# l3lanSpy.net
KiCad netlist of a schematic drawn in EAGLE
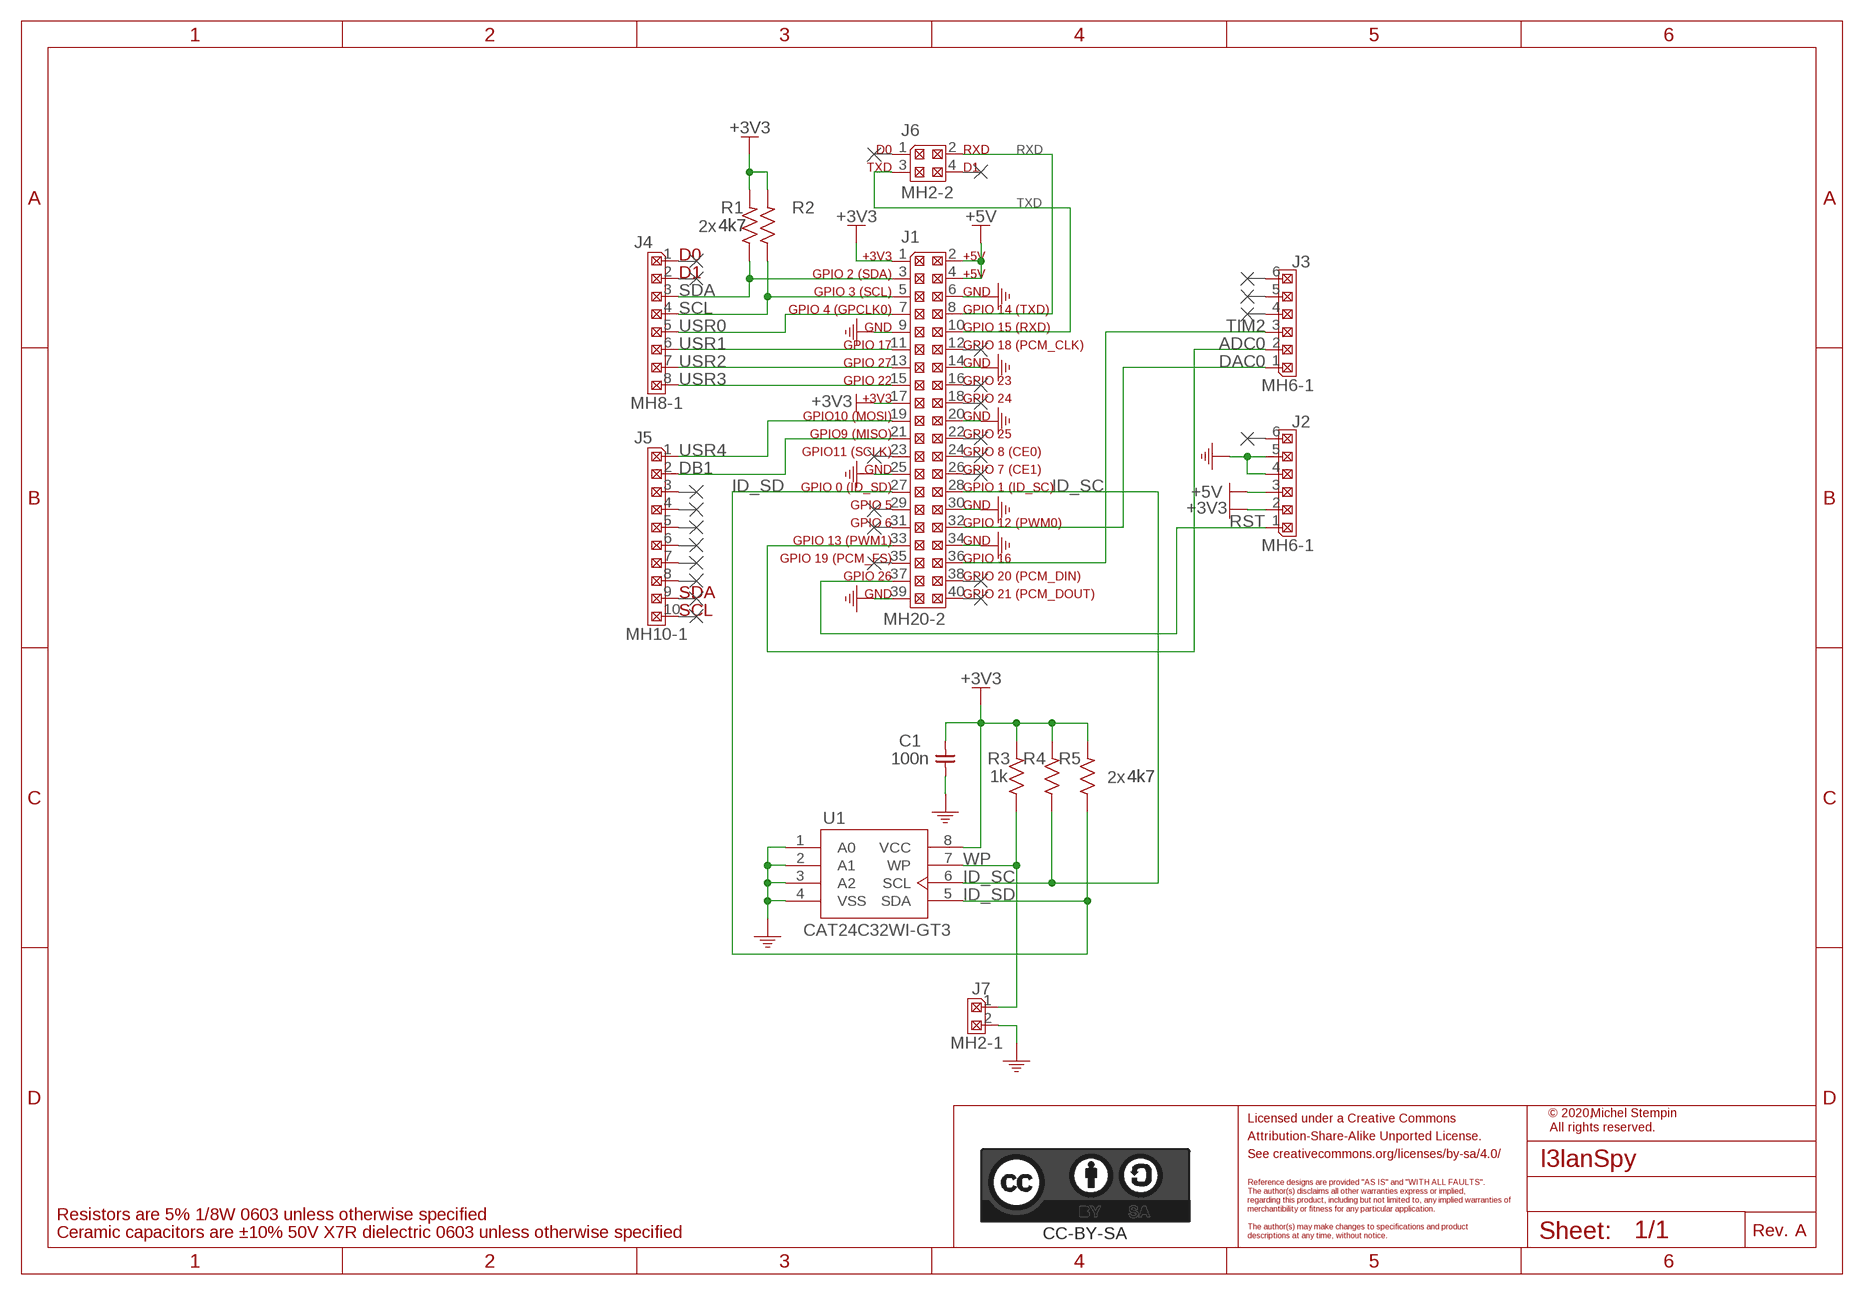
[diagram p0: schematic, sheet 1]

(export (version "E")
  (design (tool "Eeschema 10.0.6"))
  (components
    (comp (ref "C1")
      (value "100n")
      (footprint "eagle-import:C0603")
      (libsource (lib "eagle-import") (part "CAP_0603"))
    )
    (comp (ref "J1")
      (value "MH20-2")
      (footprint "eagle-import:MH20-2-0.1")
      (libsource (lib "eagle-import") (part "MH20-2"))
    )
    (comp (ref "J2")
      (value "MH6-1")
      (footprint "eagle-import:MH6-1-0.1")
      (libsource (lib "eagle-import") (part "MH6-1"))
    )
    (comp (ref "J3")
      (value "MH6-1")
      (footprint "eagle-import:MH6-1-0.1")
      (libsource (lib "eagle-import") (part "MH6-1"))
    )
    (comp (ref "J4")
      (value "MH8-1")
      (footprint "eagle-import:MH8-1-0.1")
      (libsource (lib "eagle-import") (part "MH8-1"))
    )
    (comp (ref "J5")
      (value "MH10-1")
      (footprint "eagle-import:MH10-1-0.1")
      (libsource (lib "eagle-import") (part "MH10-1"))
    )
    (comp (ref "J6")
      (value "MH2-2")
      (footprint "eagle-import:MH2-2-0.1")
      (libsource (lib "eagle-import") (part "MH2-2"))
    )
    (comp (ref "J7")
      (value "MH2-1")
      (footprint "eagle-import:MH2-1-0.1")
      (libsource (lib "eagle-import") (part "MH2-1"))
    )
    (comp (ref "LOGO1")
      (value "CC-BY-SA_LOGO")
      (footprint "eagle-import:CC-BY-SA_LOGO")
      (libsource (lib "eagle-import") (part "CC-BY-SA_LOGO"))
    )
    (comp (ref "R1")
      (value "4k7")
      (footprint "eagle-import:R0603")
      (libsource (lib "eagle-import") (part "RES_0603"))
    )
    (comp (ref "R2")
      (value "4k7")
      (footprint "eagle-import:R0603")
      (libsource (lib "eagle-import") (part "RES_0603"))
    )
    (comp (ref "R3")
      (value "1k")
      (footprint "eagle-import:R0603")
      (libsource (lib "eagle-import") (part "RES_0603"))
    )
    (comp (ref "R4")
      (value "4k7")
      (footprint "eagle-import:R0603")
      (libsource (lib "eagle-import") (part "RES_0603"))
    )
    (comp (ref "R5")
      (value "4k7")
      (footprint "eagle-import:R0603")
      (libsource (lib "eagle-import") (part "RES_0603"))
    )
    (comp (ref "U1")
      (value "CAT24C32WI-GT3")
      (footprint "eagle-import:SOIC-8")
      (libsource (lib "eagle-import") (part "CAT24C32WI-GT3"))
    )
  )
  (nets
    (net (code "1") (name "+3V3") (class "Default")
      (node (ref "C1") (pin "1") (pinfunction "1_1") (pintype "passive"))
      (node (ref "J1") (pin "1") (pinfunction "1_1") (pintype "passive"))
      (node (ref "J1") (pin "17") (pinfunction "17_17") (pintype "passive"))
      (node (ref "J2") (pin "2") (pinfunction "2_2") (pintype "passive"))
      (node (ref "R1") (pin "2") (pinfunction "2_2") (pintype "passive"))
      (node (ref "R2") (pin "2") (pinfunction "2_2") (pintype "passive"))
      (node (ref "R3") (pin "2") (pinfunction "2_2") (pintype "passive"))
      (node (ref "R4") (pin "2") (pinfunction "2_2") (pintype "passive"))
      (node (ref "R5") (pin "2") (pinfunction "2_2") (pintype "passive"))
      (node (ref "U1") (pin "8") (pinfunction "VCC_8") (pintype "power_in"))
    )
    (net (code "2") (name "+5V") (class "Default")
      (node (ref "J1") (pin "2") (pinfunction "2_2") (pintype "passive"))
      (node (ref "J1") (pin "4") (pinfunction "4_4") (pintype "passive"))
      (node (ref "J2") (pin "3") (pinfunction "3_3") (pintype "passive"))
    )
    (net (code "3") (name "/ADC0") (class "Default")
      (node (ref "J1") (pin "33") (pinfunction "33_33") (pintype "passive"))
      (node (ref "J3") (pin "2") (pinfunction "2_2") (pintype "passive"))
    )
    (net (code "4") (name "/DAC0") (class "Default")
      (node (ref "J1") (pin "32") (pinfunction "32_32") (pintype "passive"))
      (node (ref "J3") (pin "1") (pinfunction "1_1") (pintype "passive"))
    )
    (net (code "5") (name "/DB1") (class "Default")
      (node (ref "J1") (pin "21") (pinfunction "21_21") (pintype "passive"))
      (node (ref "J5") (pin "2") (pinfunction "2_2") (pintype "passive"))
    )
    (net (code "6") (name "/ID_SC") (class "Default")
      (node (ref "J1") (pin "28") (pinfunction "28_28") (pintype "passive"))
      (node (ref "R4") (pin "1") (pinfunction "1_1") (pintype "passive"))
      (node (ref "U1") (pin "6") (pinfunction "SCL_6") (pintype "input"))
    )
    (net (code "7") (name "/ID_SD") (class "Default")
      (node (ref "J1") (pin "27") (pinfunction "27_27") (pintype "passive"))
      (node (ref "R5") (pin "1") (pinfunction "1_1") (pintype "passive"))
      (node (ref "U1") (pin "5") (pinfunction "SDA_5") (pintype "bidirectional"))
    )
    (net (code "8") (name "/RST") (class "Default")
      (node (ref "J1") (pin "37") (pinfunction "37_37") (pintype "passive"))
      (node (ref "J2") (pin "1") (pinfunction "1_1") (pintype "passive"))
    )
    (net (code "9") (name "/RXD") (class "Default")
      (node (ref "J1") (pin "8") (pinfunction "8_8") (pintype "passive"))
      (node (ref "J6") (pin "2") (pinfunction "2_2") (pintype "passive"))
    )
    (net (code "10") (name "/SCL") (class "Default")
      (node (ref "J1") (pin "5") (pinfunction "5_5") (pintype "passive"))
      (node (ref "J4") (pin "4") (pinfunction "4_4") (pintype "passive"))
      (node (ref "R2") (pin "1") (pinfunction "1_1") (pintype "passive"))
    )
    (net (code "11") (name "/SDA") (class "Default")
      (node (ref "J1") (pin "3") (pinfunction "3_3") (pintype "passive"))
      (node (ref "J4") (pin "3") (pinfunction "3_3") (pintype "passive"))
      (node (ref "R1") (pin "1") (pinfunction "1_1") (pintype "passive"))
    )
    (net (code "12") (name "/TIM2") (class "Default")
      (node (ref "J1") (pin "36") (pinfunction "36_36") (pintype "passive"))
      (node (ref "J3") (pin "3") (pinfunction "3_3") (pintype "passive"))
    )
    (net (code "13") (name "/TXD") (class "Default")
      (node (ref "J1") (pin "10") (pinfunction "10_10") (pintype "passive"))
      (node (ref "J6") (pin "3") (pinfunction "3_3") (pintype "passive"))
    )
    (net (code "14") (name "/USR0") (class "Default")
      (node (ref "J1") (pin "7") (pinfunction "7_7") (pintype "passive"))
      (node (ref "J4") (pin "5") (pinfunction "5_5") (pintype "passive"))
    )
    (net (code "15") (name "/USR1") (class "Default")
      (node (ref "J1") (pin "11") (pinfunction "11_11") (pintype "passive"))
      (node (ref "J4") (pin "6") (pinfunction "6_6") (pintype "passive"))
    )
    (net (code "16") (name "/USR2") (class "Default")
      (node (ref "J1") (pin "13") (pinfunction "13_13") (pintype "passive"))
      (node (ref "J4") (pin "7") (pinfunction "7_7") (pintype "passive"))
    )
    (net (code "17") (name "/USR3") (class "Default")
      (node (ref "J1") (pin "15") (pinfunction "15_15") (pintype "passive"))
      (node (ref "J4") (pin "8") (pinfunction "8_8") (pintype "passive"))
    )
    (net (code "18") (name "/USR4") (class "Default")
      (node (ref "J1") (pin "19") (pinfunction "19_19") (pintype "passive"))
      (node (ref "J5") (pin "1") (pinfunction "1_1") (pintype "passive"))
    )
    (net (code "19") (name "/WP") (class "Default")
      (node (ref "J7") (pin "1") (pinfunction "1_1") (pintype "passive"))
      (node (ref "R3") (pin "1") (pinfunction "1_1") (pintype "passive"))
      (node (ref "U1") (pin "7") (pinfunction "WP_7") (pintype "input"))
    )
    (net (code "20") (name "GND") (class "Default")
      (node (ref "C1") (pin "2") (pinfunction "2_2") (pintype "passive"))
      (node (ref "J1") (pin "14") (pinfunction "14_14") (pintype "passive"))
      (node (ref "J1") (pin "20") (pinfunction "20_20") (pintype "passive"))
      (node (ref "J1") (pin "25") (pinfunction "25_25") (pintype "passive"))
      (node (ref "J1") (pin "30") (pinfunction "30_30") (pintype "passive"))
      (node (ref "J1") (pin "34") (pinfunction "34_34") (pintype "passive"))
      (node (ref "J1") (pin "39") (pinfunction "39_39") (pintype "passive"))
      (node (ref "J1") (pin "6") (pinfunction "6_6") (pintype "passive"))
      (node (ref "J1") (pin "9") (pinfunction "9_9") (pintype "passive"))
      (node (ref "J2") (pin "4") (pinfunction "4_4") (pintype "passive"))
      (node (ref "J2") (pin "5") (pinfunction "5_5") (pintype "passive"))
      (node (ref "J7") (pin "2") (pinfunction "2_2") (pintype "passive"))
      (node (ref "U1") (pin "1") (pinfunction "A0_1") (pintype "input"))
      (node (ref "U1") (pin "2") (pinfunction "A1_2") (pintype "input"))
      (node (ref "U1") (pin "3") (pinfunction "A2_3") (pintype "input"))
      (node (ref "U1") (pin "4") (pinfunction "VSS_4") (pintype "power_in"))
    )
    (net (code "21") (name "unconnected-(J1-Pad12)") (class "Default")
      (node (ref "J1") (pin "12") (pinfunction "12_12") (pintype "passive"))
    )
    (net (code "22") (name "unconnected-(J1-Pad16)") (class "Default")
      (node (ref "J1") (pin "16") (pinfunction "16_16") (pintype "passive"))
    )
    (net (code "23") (name "unconnected-(J1-Pad18)") (class "Default")
      (node (ref "J1") (pin "18") (pinfunction "18_18") (pintype "passive"))
    )
    (net (code "24") (name "unconnected-(J1-Pad22)") (class "Default")
      (node (ref "J1") (pin "22") (pinfunction "22_22") (pintype "passive"))
    )
    (net (code "25") (name "unconnected-(J1-Pad23)") (class "Default")
      (node (ref "J1") (pin "23") (pinfunction "23_23") (pintype "passive"))
    )
    (net (code "26") (name "unconnected-(J1-Pad24)") (class "Default")
      (node (ref "J1") (pin "24") (pinfunction "24_24") (pintype "passive"))
    )
    (net (code "27") (name "unconnected-(J1-Pad26)") (class "Default")
      (node (ref "J1") (pin "26") (pinfunction "26_26") (pintype "passive"))
    )
    (net (code "28") (name "unconnected-(J1-Pad29)") (class "Default")
      (node (ref "J1") (pin "29") (pinfunction "29_29") (pintype "passive"))
    )
    (net (code "29") (name "unconnected-(J1-Pad31)") (class "Default")
      (node (ref "J1") (pin "31") (pinfunction "31_31") (pintype "passive"))
    )
    (net (code "30") (name "unconnected-(J1-Pad35)") (class "Default")
      (node (ref "J1") (pin "35") (pinfunction "35_35") (pintype "passive"))
    )
    (net (code "31") (name "unconnected-(J1-Pad38)") (class "Default")
      (node (ref "J1") (pin "38") (pinfunction "38_38") (pintype "passive"))
    )
    (net (code "32") (name "unconnected-(J1-Pad40)") (class "Default")
      (node (ref "J1") (pin "40") (pinfunction "40_40") (pintype "passive"))
    )
    (net (code "33") (name "unconnected-(J2-Pad6)") (class "Default")
      (node (ref "J2") (pin "6") (pinfunction "6_6") (pintype "passive"))
    )
    (net (code "34") (name "unconnected-(J3-Pad4)") (class "Default")
      (node (ref "J3") (pin "4") (pinfunction "4_4") (pintype "passive"))
    )
    (net (code "35") (name "unconnected-(J3-Pad5)") (class "Default")
      (node (ref "J3") (pin "5") (pinfunction "5_5") (pintype "passive"))
    )
    (net (code "36") (name "unconnected-(J3-Pad6)") (class "Default")
      (node (ref "J3") (pin "6") (pinfunction "6_6") (pintype "passive"))
    )
    (net (code "37") (name "unconnected-(J4-Pad1)") (class "Default")
      (node (ref "J4") (pin "1") (pinfunction "1_1") (pintype "passive"))
    )
    (net (code "38") (name "unconnected-(J4-Pad2)") (class "Default")
      (node (ref "J4") (pin "2") (pinfunction "2_2") (pintype "passive"))
    )
    (net (code "39") (name "unconnected-(J5-Pad3)") (class "Default")
      (node (ref "J5") (pin "3") (pinfunction "3_3") (pintype "passive"))
    )
    (net (code "40") (name "unconnected-(J5-Pad4)") (class "Default")
      (node (ref "J5") (pin "4") (pinfunction "4_4") (pintype "passive"))
    )
    (net (code "41") (name "unconnected-(J5-Pad5)") (class "Default")
      (node (ref "J5") (pin "5") (pinfunction "5_5") (pintype "passive"))
    )
    (net (code "42") (name "unconnected-(J5-Pad6)") (class "Default")
      (node (ref "J5") (pin "6") (pinfunction "6_6") (pintype "passive"))
    )
    (net (code "43") (name "unconnected-(J5-Pad7)") (class "Default")
      (node (ref "J5") (pin "7") (pinfunction "7_7") (pintype "passive"))
    )
    (net (code "44") (name "unconnected-(J5-Pad8)") (class "Default")
      (node (ref "J5") (pin "8") (pinfunction "8_8") (pintype "passive"))
    )
    (net (code "45") (name "unconnected-(J5-Pad9)") (class "Default")
      (node (ref "J5") (pin "9") (pinfunction "9_9") (pintype "passive"))
    )
    (net (code "46") (name "unconnected-(J5-Pad10)") (class "Default")
      (node (ref "J5") (pin "10") (pinfunction "10_10") (pintype "passive"))
    )
    (net (code "47") (name "unconnected-(J6-Pad1)") (class "Default")
      (node (ref "J6") (pin "1") (pinfunction "1_1") (pintype "passive"))
    )
    (net (code "48") (name "unconnected-(J6-Pad4)") (class "Default")
      (node (ref "J6") (pin "4") (pinfunction "4_4") (pintype "passive"))
    )
  )
)
